# Drivers.net
KiCad netlist of a schematic drawn in Altium Designer
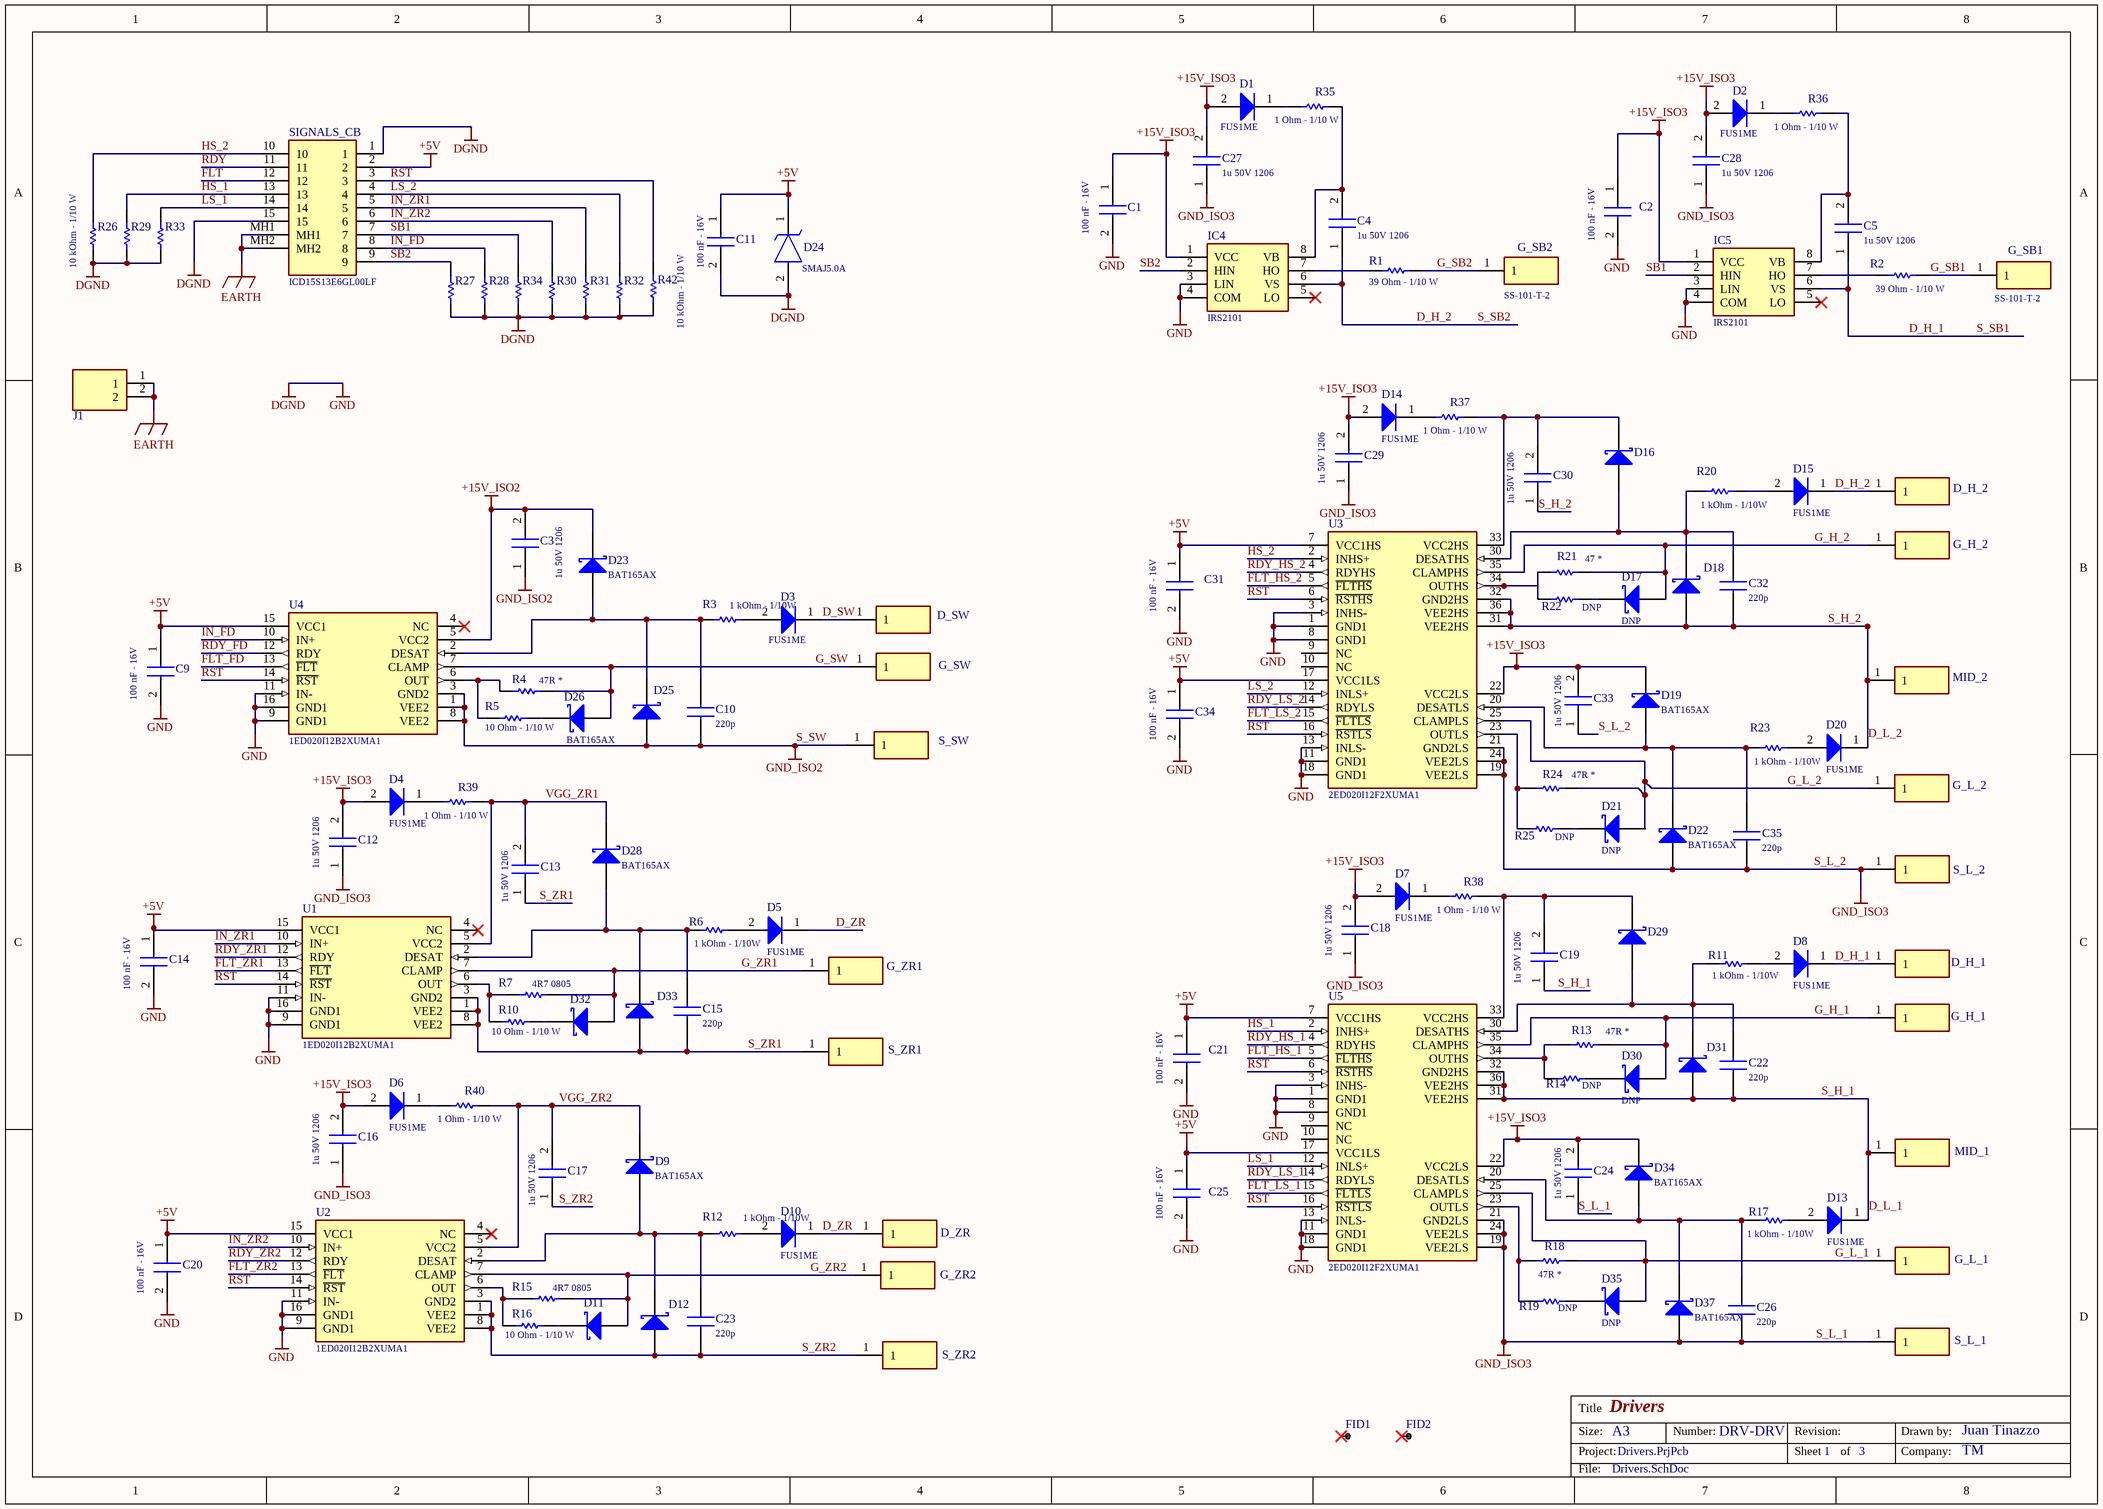
[diagram p0: Drivers.SchDoc]

(export (version "E")
  (design (tool "Eeschema 10.0.6"))
  (components
    (comp (ref "C1")
      (value "100 nF - 16V")
      (footprint "CAPC1608X95N")
      (description "Capacitor")
      (fields
        (field (name "MANUFACTURER_PART_NUMBER") "EMK107B7104KA-T")
        (field (name "MOUSER PART NUMBER") "963-EMK107B7104KA-T")
      )
      (libsource (lib "SamacSys") (part "EMK107B7104KA-T"))
    )
    (comp (ref "C2")
      (value "100 nF - 16V")
      (footprint "CAPC1608X95N")
      (description "Capacitor")
      (fields
        (field (name "MANUFACTURER_PART_NUMBER") "EMK107B7104KA-T")
        (field (name "MOUSER PART NUMBER") "963-EMK107B7104KA-T")
      )
      (libsource (lib "SamacSys") (part "EMK107B7104KA-T"))
    )
    (comp (ref "C3")
      (value "1u 50V 1206")
      (footprint "SamacSys:CAPC3216X180N")
      (description "Capacitor")
      (fields
        (field (name "MANUFACTURER_PART_NUMBER") "C3216X7R1H105K160AE")
        (field (name "MOUSER PART NUMBER") "810-C3216X7R1H105KST")
      )
      (libsource (lib "*") (part "C3216X7R1H105K160AE"))
    )
    (comp (ref "C4")
      (value "1u 50V 1206")
      (footprint "SamacSys:CAPC3216X180N")
      (description "Capacitor")
      (fields
        (field (name "MANUFACTURER_PART_NUMBER") "C3216X7R1H105K160AE")
        (field (name "MOUSER PART NUMBER") "810-C3216X7R1H105KST")
      )
      (libsource (lib "*") (part "C3216X7R1H105K160AE"))
    )
    (comp (ref "C5")
      (value "1u 50V 1206")
      (footprint "SamacSys:CAPC3216X180N")
      (description "Capacitor")
      (fields
        (field (name "MANUFACTURER_PART_NUMBER") "C3216X7R1H105K160AE")
        (field (name "MOUSER PART NUMBER") "810-C3216X7R1H105KST")
      )
      (libsource (lib "*") (part "C3216X7R1H105K160AE"))
    )
    (comp (ref "C9")
      (value "100 nF - 16V")
      (footprint "CAPC1608X95N")
      (description "Capacitor")
      (fields
        (field (name "MANUFACTURER_PART_NUMBER") "EMK107B7104KA-T")
        (field (name "MOUSER PART NUMBER") "963-EMK107B7104KA-T")
      )
      (libsource (lib "SamacSys") (part "EMK107B7104KA-T"))
    )
    (comp (ref "C10")
      (value "220p")
      (footprint "C0603")
      (description "Capacitor")
      (fields
        (field (name "MANUFACTURER_PART_NUMBER") "C0603C221J5HACAUTO")
        (field (name "MOUSER PART NUMBER") "80-C0603C221J5HAUTO")
      )
      (libsource (lib "SamacSys") (part "C0603C221J5HACAUTO"))
    )
    (comp (ref "C11")
      (value "100 nF - 16V")
      (footprint "CAPC1608X95N")
      (description "Capacitor")
      (fields
        (field (name "MANUFACTURER_PART_NUMBER") "EMK107B7104KA-T")
        (field (name "MOUSER PART NUMBER") "963-EMK107B7104KA-T")
      )
      (libsource (lib "SamacSys") (part "EMK107B7104KA-T"))
    )
    (comp (ref "C12")
      (value "1u 50V 1206")
      (footprint "SamacSys:CAPC3216X180N")
      (description "Capacitor")
      (fields
        (field (name "MANUFACTURER_PART_NUMBER") "C3216X7R1H105K160AE")
        (field (name "MOUSER PART NUMBER") "810-C3216X7R1H105KST")
      )
      (libsource (lib "*") (part "C3216X7R1H105K160AE"))
    )
    (comp (ref "C13")
      (value "1u 50V 1206")
      (footprint "SamacSys:CAPC3216X180N")
      (description "Capacitor")
      (fields
        (field (name "MANUFACTURER_PART_NUMBER") "C3216X7R1H105K160AE")
        (field (name "MOUSER PART NUMBER") "810-C3216X7R1H105KST")
      )
      (libsource (lib "*") (part "C3216X7R1H105K160AE"))
    )
    (comp (ref "C14")
      (value "100 nF - 16V")
      (footprint "CAPC1608X95N")
      (description "Capacitor")
      (fields
        (field (name "MANUFACTURER_PART_NUMBER") "EMK107B7104KA-T")
        (field (name "MOUSER PART NUMBER") "963-EMK107B7104KA-T")
      )
      (libsource (lib "SamacSys") (part "EMK107B7104KA-T"))
    )
    (comp (ref "C15")
      (value "220p")
      (footprint "C0603")
      (description "Capacitor")
      (fields
        (field (name "MANUFACTURER_PART_NUMBER") "C0603C221J5HACAUTO")
        (field (name "MOUSER PART NUMBER") "80-C0603C221J5HAUTO")
      )
      (libsource (lib "SamacSys") (part "C0603C221J5HACAUTO"))
    )
    (comp (ref "C16")
      (value "1u 50V 1206")
      (footprint "SamacSys:CAPC3216X180N")
      (description "Capacitor")
      (fields
        (field (name "MANUFACTURER_PART_NUMBER") "C3216X7R1H105K160AE")
        (field (name "MOUSER PART NUMBER") "810-C3216X7R1H105KST")
      )
      (libsource (lib "*") (part "C3216X7R1H105K160AE"))
    )
    (comp (ref "C17")
      (value "1u 50V 1206")
      (footprint "SamacSys:CAPC3216X180N")
      (description "Capacitor")
      (fields
        (field (name "MANUFACTURER_PART_NUMBER") "C3216X7R1H105K160AE")
        (field (name "MOUSER PART NUMBER") "810-C3216X7R1H105KST")
      )
      (libsource (lib "*") (part "C3216X7R1H105K160AE"))
    )
    (comp (ref "C18")
      (value "1u 50V 1206")
      (footprint "SamacSys:CAPC3216X180N")
      (description "Capacitor")
      (fields
        (field (name "MANUFACTURER_PART_NUMBER") "C3216X7R1H105K160AE")
        (field (name "MOUSER PART NUMBER") "810-C3216X7R1H105KST")
      )
      (libsource (lib "*") (part "C3216X7R1H105K160AE"))
    )
    (comp (ref "C19")
      (value "1u 50V 1206")
      (footprint "SamacSys:CAPC3216X180N")
      (description "Capacitor")
      (fields
        (field (name "MANUFACTURER_PART_NUMBER") "C3216X7R1H105K160AE")
        (field (name "MOUSER PART NUMBER") "810-C3216X7R1H105KST")
      )
      (libsource (lib "*") (part "C3216X7R1H105K160AE"))
    )
    (comp (ref "C20")
      (value "100 nF - 16V")
      (footprint "CAPC1608X95N")
      (description "Capacitor")
      (fields
        (field (name "MANUFACTURER_PART_NUMBER") "EMK107B7104KA-T")
        (field (name "MOUSER PART NUMBER") "963-EMK107B7104KA-T")
      )
      (libsource (lib "SamacSys") (part "EMK107B7104KA-T"))
    )
    (comp (ref "C21")
      (value "100 nF - 16V")
      (footprint "CAPC1608X95N")
      (description "Capacitor")
      (fields
        (field (name "MANUFACTURER_PART_NUMBER") "EMK107B7104KA-T")
        (field (name "MOUSER PART NUMBER") "963-EMK107B7104KA-T")
      )
      (libsource (lib "SamacSys") (part "EMK107B7104KA-T"))
    )
    (comp (ref "C22")
      (value "220p")
      (footprint "C0603")
      (description "Capacitor")
      (fields
        (field (name "MANUFACTURER_PART_NUMBER") "C0603C221J5HACAUTO")
        (field (name "MOUSER PART NUMBER") "80-C0603C221J5HAUTO")
      )
      (libsource (lib "SamacSys") (part "C0603C221J5HACAUTO"))
    )
    (comp (ref "C23")
      (value "220p")
      (footprint "C0603")
      (description "Capacitor")
      (fields
        (field (name "MANUFACTURER_PART_NUMBER") "C0603C221J5HACAUTO")
        (field (name "MOUSER PART NUMBER") "80-C0603C221J5HAUTO")
      )
      (libsource (lib "SamacSys") (part "C0603C221J5HACAUTO"))
    )
    (comp (ref "C24")
      (value "1u 50V 1206")
      (footprint "SamacSys:CAPC3216X180N")
      (description "Capacitor")
      (fields
        (field (name "MANUFACTURER_PART_NUMBER") "C3216X7R1H105K160AE")
        (field (name "MOUSER PART NUMBER") "810-C3216X7R1H105KST")
      )
      (libsource (lib "*") (part "C3216X7R1H105K160AE"))
    )
    (comp (ref "C25")
      (value "100 nF - 16V")
      (footprint "CAPC1608X95N")
      (description "Capacitor")
      (fields
        (field (name "MANUFACTURER_PART_NUMBER") "EMK107B7104KA-T")
        (field (name "MOUSER PART NUMBER") "963-EMK107B7104KA-T")
      )
      (libsource (lib "SamacSys") (part "EMK107B7104KA-T"))
    )
    (comp (ref "C26")
      (value "220p")
      (footprint "C0603")
      (description "Capacitor")
      (fields
        (field (name "MANUFACTURER_PART_NUMBER") "C0603C221J5HACAUTO")
        (field (name "MOUSER PART NUMBER") "80-C0603C221J5HAUTO")
      )
      (libsource (lib "SamacSys") (part "C0603C221J5HACAUTO"))
    )
    (comp (ref "C27")
      (value "1u 50V 1206")
      (footprint "SamacSys:CAPC3216X180N")
      (description "Capacitor")
      (fields
        (field (name "MANUFACTURER_PART_NUMBER") "C3216X7R1H105K160AE")
        (field (name "MOUSER PART NUMBER") "810-C3216X7R1H105KST")
      )
      (libsource (lib "*") (part "C3216X7R1H105K160AE"))
    )
    (comp (ref "C28")
      (value "1u 50V 1206")
      (footprint "SamacSys:CAPC3216X180N")
      (description "Capacitor")
      (fields
        (field (name "MANUFACTURER_PART_NUMBER") "C3216X7R1H105K160AE")
        (field (name "MOUSER PART NUMBER") "810-C3216X7R1H105KST")
      )
      (libsource (lib "*") (part "C3216X7R1H105K160AE"))
    )
    (comp (ref "C29")
      (value "1u 50V 1206")
      (footprint "SamacSys:CAPC3216X180N")
      (description "Capacitor")
      (fields
        (field (name "MANUFACTURER_PART_NUMBER") "C3216X7R1H105K160AE")
        (field (name "MOUSER PART NUMBER") "810-C3216X7R1H105KST")
      )
      (libsource (lib "*") (part "C3216X7R1H105K160AE"))
    )
    (comp (ref "C30")
      (value "1u 50V 1206")
      (footprint "SamacSys:CAPC3216X180N")
      (description "Capacitor")
      (fields
        (field (name "MANUFACTURER_PART_NUMBER") "C3216X7R1H105K160AE")
        (field (name "MOUSER PART NUMBER") "810-C3216X7R1H105KST")
      )
      (libsource (lib "*") (part "C3216X7R1H105K160AE"))
    )
    (comp (ref "C31")
      (value "100 nF - 16V")
      (footprint "CAPC1608X95N")
      (description "Capacitor")
      (fields
        (field (name "MANUFACTURER_PART_NUMBER") "EMK107B7104KA-T")
        (field (name "MOUSER PART NUMBER") "963-EMK107B7104KA-T")
      )
      (libsource (lib "SamacSys") (part "EMK107B7104KA-T"))
    )
    (comp (ref "C32")
      (value "220p")
      (footprint "C0603")
      (description "Capacitor")
      (fields
        (field (name "MANUFACTURER_PART_NUMBER") "C0603C221J5HACAUTO")
        (field (name "MOUSER PART NUMBER") "80-C0603C221J5HAUTO")
      )
      (libsource (lib "SamacSys") (part "C0603C221J5HACAUTO"))
    )
    (comp (ref "C33")
      (value "1u 50V 1206")
      (footprint "SamacSys:CAPC3216X180N")
      (description "Capacitor")
      (fields
        (field (name "MANUFACTURER_PART_NUMBER") "C3216X7R1H105K160AE")
        (field (name "MOUSER PART NUMBER") "810-C3216X7R1H105KST")
      )
      (libsource (lib "*") (part "C3216X7R1H105K160AE"))
    )
    (comp (ref "C34")
      (value "100 nF - 16V")
      (footprint "CAPC1608X95N")
      (description "Capacitor")
      (fields
        (field (name "MANUFACTURER_PART_NUMBER") "EMK107B7104KA-T")
        (field (name "MOUSER PART NUMBER") "963-EMK107B7104KA-T")
      )
      (libsource (lib "SamacSys") (part "EMK107B7104KA-T"))
    )
    (comp (ref "C35")
      (value "220p")
      (footprint "C0603")
      (description "Capacitor")
      (fields
        (field (name "MANUFACTURER_PART_NUMBER") "C0603C221J5HACAUTO")
        (field (name "MOUSER PART NUMBER") "80-C0603C221J5HAUTO")
      )
      (libsource (lib "SamacSys") (part "C0603C221J5HACAUTO"))
    )
    (comp (ref "D1")
      (value "FUS1ME")
      (footprint "SamacSys:SODFL3718X120N")
      (description "Diode")
      (fields (field (name "MOUSER PART NUMBER") "621-FUS1ME"))
      (libsource (lib "SamacSys") (part "FUS1ME"))
    )
    (comp (ref "D2")
      (value "FUS1ME")
      (footprint "SamacSys:SODFL3718X120N")
      (description "Diode")
      (fields (field (name "MOUSER PART NUMBER") "621-FUS1ME"))
      (libsource (lib "SamacSys") (part "FUS1ME"))
    )
    (comp (ref "D3")
      (value "FUS1ME")
      (footprint "SamacSys:SODFL3718X120N")
      (description "Diode")
      (fields (field (name "MOUSER PART NUMBER") "621-FUS1ME"))
      (libsource (lib "SamacSys") (part "FUS1ME"))
    )
    (comp (ref "D4")
      (value "FUS1ME")
      (footprint "SamacSys:SODFL3718X120N")
      (description "Diode")
      (fields (field (name "MOUSER PART NUMBER") "621-FUS1ME"))
      (libsource (lib "SamacSys") (part "FUS1ME"))
    )
    (comp (ref "D5")
      (value "FUS1ME")
      (footprint "SamacSys:SODFL3718X120N")
      (description "Diode")
      (fields (field (name "MOUSER PART NUMBER") "621-FUS1ME"))
      (libsource (lib "SamacSys") (part "FUS1ME"))
    )
    (comp (ref "D6")
      (value "FUS1ME")
      (footprint "SamacSys:SODFL3718X120N")
      (description "Diode")
      (fields (field (name "MOUSER PART NUMBER") "621-FUS1ME"))
      (libsource (lib "SamacSys") (part "FUS1ME"))
    )
    (comp (ref "D7")
      (value "FUS1ME")
      (footprint "SamacSys:SODFL3718X120N")
      (description "Diode")
      (fields (field (name "MOUSER PART NUMBER") "621-FUS1ME"))
      (libsource (lib "SamacSys") (part "FUS1ME"))
    )
    (comp (ref "D8")
      (value "FUS1ME")
      (footprint "SamacSys:SODFL3718X120N")
      (description "Diode")
      (fields (field (name "MOUSER PART NUMBER") "621-FUS1ME"))
      (libsource (lib "SamacSys") (part "FUS1ME"))
    )
    (comp (ref "D9")
      (value "BAT165AX")
      (footprint "BAT165AX")
      (description "Schottky Diode")
      (fields (field (name "MOUSER PART NUMBER") "771-BAT165AX"))
      (libsource (lib "SamacSys") (part "BAT165AX"))
    )
    (comp (ref "D10")
      (value "FUS1ME")
      (footprint "SamacSys:SODFL3718X120N")
      (description "Diode")
      (fields (field (name "MOUSER PART NUMBER") "621-FUS1ME"))
      (libsource (lib "SamacSys") (part "FUS1ME"))
    )
    (comp (ref "D11")
      (value "BAT165AX")
      (footprint "BAT165AX")
      (description "Schottky Diode")
      (fields (field (name "MOUSER PART NUMBER") "771-BAT165AX"))
      (libsource (lib "SamacSys") (part "BAT165AX"))
    )
    (comp (ref "D12")
      (value "BAT165AX")
      (footprint "BAT165AX")
      (description "Schottky Diode")
      (fields (field (name "MOUSER PART NUMBER") "771-BAT165AX"))
      (libsource (lib "SamacSys") (part "BAT165AX"))
    )
    (comp (ref "D13")
      (value "FUS1ME")
      (footprint "SamacSys:SODFL3718X120N")
      (description "Diode")
      (fields (field (name "MOUSER PART NUMBER") "621-FUS1ME"))
      (libsource (lib "SamacSys") (part "FUS1ME"))
    )
    (comp (ref "D14")
      (value "FUS1ME")
      (footprint "SamacSys:SODFL3718X120N")
      (description "Diode")
      (fields (field (name "MOUSER PART NUMBER") "621-FUS1ME"))
      (libsource (lib "SamacSys") (part "FUS1ME"))
    )
    (comp (ref "D15")
      (value "FUS1ME")
      (footprint "SamacSys:SODFL3718X120N")
      (description "Diode")
      (fields (field (name "MOUSER PART NUMBER") "621-FUS1ME"))
      (libsource (lib "SamacSys") (part "FUS1ME"))
    )
    (comp (ref "D16")
      (value "BAT165AX")
      (footprint "BAT165AX")
      (description "Schottky Diode")
      (fields (field (name "MOUSER PART NUMBER") "771-BAT165AX"))
      (libsource (lib "SamacSys") (part "BAT165AX"))
    )
    (comp (ref "D17")
      (value "DNP")
      (footprint "BAT165AX")
      (description "Schottky Diode")
      (fields
        (field (name "MANUFACTURER_PART_NUMBER") "BAT165AX")
        (field (name "MOUSER PART NUMBER") "771-BAT165AX")
      )
      (libsource (lib "SamacSys") (part "BAT165AX"))
    )
    (comp (ref "D18")
      (value "BAT165AX")
      (footprint "BAT165AX")
      (description "Schottky Diode")
      (fields (field (name "MOUSER PART NUMBER") "771-BAT165AX"))
      (libsource (lib "SamacSys") (part "BAT165AX"))
    )
    (comp (ref "D19")
      (value "BAT165AX")
      (footprint "BAT165AX")
      (description "Schottky Diode")
      (fields (field (name "MOUSER PART NUMBER") "771-BAT165AX"))
      (libsource (lib "SamacSys") (part "BAT165AX"))
    )
    (comp (ref "D20")
      (value "FUS1ME")
      (footprint "SamacSys:SODFL3718X120N")
      (description "Diode")
      (fields (field (name "MOUSER PART NUMBER") "621-FUS1ME"))
      (libsource (lib "SamacSys") (part "FUS1ME"))
    )
    (comp (ref "D21")
      (value "DNP")
      (footprint "BAT165AX")
      (description "Schottky Diode")
      (fields
        (field (name "MANUFACTURER_PART_NUMBER") "BAT165AX")
        (field (name "MOUSER PART NUMBER") "771-BAT165AX")
      )
      (libsource (lib "SamacSys") (part "BAT165AX"))
    )
    (comp (ref "D22")
      (value "BAT165AX")
      (footprint "BAT165AX")
      (description "Schottky Diode")
      (fields (field (name "MOUSER PART NUMBER") "771-BAT165AX"))
      (libsource (lib "SamacSys") (part "BAT165AX"))
    )
    (comp (ref "D23")
      (value "BAT165AX")
      (footprint "BAT165AX")
      (description "Schottky Diode")
      (fields (field (name "MOUSER PART NUMBER") "771-BAT165AX"))
      (libsource (lib "SamacSys") (part "BAT165AX"))
    )
    (comp (ref "D24")
      (value "SMAJ5.0A")
      (footprint "DIOM5026X229N")
      (description "TVS Diode (Uni-directional)")
      (fields (field (name "MOUSER PART NUMBER") "576-SMAJ5.0A"))
      (libsource (lib "SamacSys") (part "SMAJ5.0A"))
    )
    (comp (ref "D25")
      (value "BAT165AX")
      (footprint "BAT165AX")
      (description "Schottky Diode")
      (fields (field (name "MOUSER PART NUMBER") "771-BAT165AX"))
      (libsource (lib "SamacSys") (part "BAT165AX"))
    )
    (comp (ref "D26")
      (value "BAT165AX")
      (footprint "BAT165AX")
      (description "Schottky Diode")
      (fields (field (name "MOUSER PART NUMBER") "771-BAT165AX"))
      (libsource (lib "SamacSys") (part "BAT165AX"))
    )
    (comp (ref "D28")
      (value "BAT165AX")
      (footprint "BAT165AX")
      (description "Schottky Diode")
      (fields (field (name "MOUSER PART NUMBER") "771-BAT165AX"))
      (libsource (lib "SamacSys") (part "BAT165AX"))
    )
    (comp (ref "D29")
      (value "BAT165AX")
      (footprint "BAT165AX")
      (description "Schottky Diode")
      (fields (field (name "MOUSER PART NUMBER") "771-BAT165AX"))
      (libsource (lib "SamacSys") (part "BAT165AX"))
    )
    (comp (ref "D30")
      (value "DNP")
      (footprint "BAT165AX")
      (description "Schottky Diode")
      (fields
        (field (name "MANUFACTURER_PART_NUMBER") "BAT165AX")
        (field (name "MOUSER PART NUMBER") "771-BAT165AX")
      )
      (libsource (lib "SamacSys") (part "BAT165AX"))
    )
    (comp (ref "D31")
      (value "BAT165AX")
      (footprint "BAT165AX")
      (description "Schottky Diode")
      (fields (field (name "MOUSER PART NUMBER") "771-BAT165AX"))
      (libsource (lib "SamacSys") (part "BAT165AX"))
    )
    (comp (ref "D32")
      (value "BAT165AX")
      (footprint "BAT165AX")
      (description "Schottky Diode")
      (fields (field (name "MOUSER PART NUMBER") "771-BAT165AX"))
      (libsource (lib "SamacSys") (part "BAT165AX"))
    )
    (comp (ref "D33")
      (value "BAT165AX")
      (footprint "BAT165AX")
      (description "Schottky Diode")
      (fields (field (name "MOUSER PART NUMBER") "771-BAT165AX"))
      (libsource (lib "SamacSys") (part "BAT165AX"))
    )
    (comp (ref "D34")
      (value "BAT165AX")
      (footprint "BAT165AX")
      (description "Schottky Diode")
      (fields (field (name "MOUSER PART NUMBER") "771-BAT165AX"))
      (libsource (lib "SamacSys") (part "BAT165AX"))
    )
    (comp (ref "D35")
      (value "DNP")
      (footprint "BAT165AX")
      (description "Schottky Diode")
      (fields
        (field (name "MANUFACTURER_PART_NUMBER") "BAT165AX")
        (field (name "MOUSER PART NUMBER") "771-BAT165AX")
      )
      (libsource (lib "SamacSys") (part "BAT165AX"))
    )
    (comp (ref "D37")
      (value "BAT165AX")
      (footprint "BAT165AX")
      (description "Schottky Diode")
      (fields (field (name "MOUSER PART NUMBER") "771-BAT165AX"))
      (libsource (lib "SamacSys") (part "BAT165AX"))
    )
    (comp (ref "D_H_1")
      (value "SS-101-T-2")
      (footprint "SS-101-XX-2")
      (description "Connector")
      (fields (field (name "MOUSER PART NUMBER") "200-SS101T2"))
      (libsource (lib "SamacSys") (part "SS-101-T-2"))
    )
    (comp (ref "D_H_2")
      (value "SS-101-T-2")
      (footprint "SS-101-XX-2")
      (description "Connector")
      (fields (field (name "MOUSER PART NUMBER") "200-SS101T2"))
      (libsource (lib "SamacSys") (part "SS-101-T-2"))
    )
    (comp (ref "D_SW")
      (value "D_SW")
      (footprint "SS-101-XX-2")
      (description "Connector")
      (fields
        (field (name "MOUSER PART NUMBER") "200-SS101T2")
        (field (name "MANUFACTURER_PART_NUMBER") "SS-101-T-2")
      )
      (libsource (lib "SamacSys") (part "SS-101-T-2"))
    )
    (comp (ref "D_ZR")
      (value "SS-101-T-2")
      (footprint "SS-101-XX-2")
      (description "Connector")
      (fields (field (name "MOUSER PART NUMBER") "200-SS101T2"))
      (libsource (lib "SamacSys") (part "SS-101-T-2"))
    )
    (comp (ref "FID1")
      (value "Fiducial")
      (footprint "Fiducial")
      (libsource (lib "Libreria1") (part "Fiducial"))
    )
    (comp (ref "FID2")
      (value "Fiducial")
      (footprint "Fiducial")
      (libsource (lib "Libreria1") (part "Fiducial"))
    )
    (comp (ref "G_H_1")
      (value "SS-101-T-2")
      (footprint "SS-101-XX-2")
      (description "Connector")
      (fields (field (name "MOUSER PART NUMBER") "200-SS101T2"))
      (libsource (lib "SamacSys") (part "SS-101-T-2"))
    )
    (comp (ref "G_H_2")
      (value "SS-101-T-2")
      (footprint "SS-101-XX-2")
      (description "Connector")
      (fields (field (name "MOUSER PART NUMBER") "200-SS101T2"))
      (libsource (lib "SamacSys") (part "SS-101-T-2"))
    )
    (comp (ref "G_L_1")
      (value "SS-101-T-2")
      (footprint "SS-101-XX-2")
      (description "Connector")
      (fields (field (name "MOUSER PART NUMBER") "200-SS101T2"))
      (libsource (lib "SamacSys") (part "SS-101-T-2"))
    )
    (comp (ref "G_L_2")
      (value "SS-101-T-2")
      (footprint "SS-101-XX-2")
      (description "Connector")
      (fields (field (name "MOUSER PART NUMBER") "200-SS101T2"))
      (libsource (lib "SamacSys") (part "SS-101-T-2"))
    )
    (comp (ref "G_SB1")
      (value "SS-101-T-2")
      (footprint "SS-101-XX-2")
      (description "Connector")
      (fields (field (name "MOUSER PART NUMBER") "200-SS101T2"))
      (libsource (lib "SamacSys") (part "SS-101-T-2"))
    )
    (comp (ref "G_SB2")
      (value "SS-101-T-2")
      (footprint "SS-101-XX-2")
      (description "Connector")
      (fields (field (name "MOUSER PART NUMBER") "200-SS101T2"))
      (libsource (lib "SamacSys") (part "SS-101-T-2"))
    )
    (comp (ref "G_SW")
      (value "G_SW")
      (footprint "SS-101-XX-2")
      (description "Connector")
      (fields
        (field (name "MOUSER PART NUMBER") "200-SS101T2")
        (field (name "MANUFACTURER_PART_NUMBER") "SS-101-T-2")
      )
      (libsource (lib "SamacSys") (part "SS-101-T-2"))
    )
    (comp (ref "G_ZR1")
      (value "SS-101-T-2")
      (footprint "SS-101-XX-2")
      (description "Connector")
      (fields (field (name "MOUSER PART NUMBER") "200-SS101T2"))
      (libsource (lib "SamacSys") (part "SS-101-T-2"))
    )
    (comp (ref "G_ZR2")
      (value "SS-101-T-2")
      (footprint "SS-101-XX-2")
      (description "Connector")
      (fields (field (name "MOUSER PART NUMBER") "200-SS101T2"))
      (libsource (lib "SamacSys") (part "SS-101-T-2"))
    )
    (comp (ref "IC4")
      (value "IRS2101")
      (footprint "SamacSys:SOIC127P600X175-8N")
      (description "Integrated Circuit")
      (fields
        (field (name "MANUFACTURER_PART_NUMBER") "IRS2101STRPBF")
        (field (name "MOUSER PART NUMBER") "942-IRS2101STRPBF")
      )
      (libsource (lib "*") (part "IRS2101STRPBF"))
    )
    (comp (ref "IC5")
      (value "IRS2101")
      (footprint "SamacSys:SOIC127P600X175-8N")
      (description "Integrated Circuit")
      (fields
        (field (name "MANUFACTURER_PART_NUMBER") "IRS2101STRPBF")
        (field (name "MOUSER PART NUMBER") "942-IRS2101STRPBF")
      )
      (libsource (lib "*") (part "IRS2101STRPBF"))
    )
    (comp (ref "J1")
      (value "19705-4303")
      (footprint "197054303")
      (description "Connector")
      (libsource (lib "SamacSys") (part "19705-4303"))
    )
    (comp (ref "MID_1")
      (value "SS-101-T-2")
      (footprint "SS-101-XX-2")
      (description "Connector")
      (fields (field (name "MOUSER PART NUMBER") "200-SS101T2"))
      (libsource (lib "SamacSys") (part "SS-101-T-2"))
    )
    (comp (ref "MID_2")
      (value "SS-101-T-2")
      (footprint "SS-101-XX-2")
      (description "Connector")
      (fields (field (name "MOUSER PART NUMBER") "200-SS101T2"))
      (libsource (lib "SamacSys") (part "SS-101-T-2"))
    )
    (comp (ref "R1")
      (value "39 Ohm - 1/10 W")
      (footprint "RESC1608X55N")
      (description "Resistor")
      (fields
        (field (name "MANUFACTURER_PART_NUMBER") "CRCW0603150RFKEBC")
        (field (name "MOUSER PART NUMBER") "71-CRCW0603150RFKEBC")
      )
      (libsource (lib "SamacSys") (part "CRCW0603150RFKEBC"))
    )
    (comp (ref "R2")
      (value "39 Ohm - 1/10 W")
      (footprint "RESC1608X55N")
      (description "Resistor")
      (fields
        (field (name "MANUFACTURER_PART_NUMBER") "CRCW0603150RFKEBC")
        (field (name "MOUSER PART NUMBER") "71-CRCW0603150RFKEBC")
      )
      (libsource (lib "SamacSys") (part "CRCW0603150RFKEBC"))
    )
    (comp (ref "R3")
      (value "1 kOhm - 1/10W")
      (footprint "RESC1608X55N")
      (description "Resistor")
      (fields
        (field (name "MANUFACTURER_PART_NUMBER") "CRCW06031K00FKEAC")
        (field (name "MOUSER PART NUMBER") "71-CRCW06031K00FKEAC")
      )
      (libsource (lib "SamacSys") (part "CRCW06031K00FKEAC"))
    )
    (comp (ref "R4")
      (value "47R *")
      (footprint "SamacSys:RESC2012X60N")
      (description "Resistor")
      (fields
        (field (name "MANUFACTURER_PART_NUMBER") "CR0805-J/-4R7ELF")
        (field (name "MOUSER PART NUMBER") "652-CR0805-J/-4R7ELF")
      )
      (libsource (lib "SamacSys") (part "CR0805-J_-4R7ELF"))
    )
    (comp (ref "R5")
      (value "10 Ohm - 1/10 W")
      (footprint "RESC1608X50N")
      (description "Resistor")
      (fields
        (field (name "MANUFACTURER_PART_NUMBER") "CRCW060310R0FKEAHP")
        (field (name "MOUSER PART NUMBER") "71-CRCW060310R0FKEAH")
      )
      (libsource (lib "SamacSys") (part "CRCW060310R0FKEAHP"))
    )
    (comp (ref "R6")
      (value "1 kOhm - 1/10W")
      (footprint "RESC1608X55N")
      (description "Resistor")
      (fields
        (field (name "MANUFACTURER_PART_NUMBER") "CRCW06031K00FKEAC")
        (field (name "MOUSER PART NUMBER") "71-CRCW06031K00FKEAC")
      )
      (libsource (lib "SamacSys") (part "CRCW06031K00FKEAC"))
    )
    (comp (ref "R7")
      (value "4R7 0805")
      (footprint "SamacSys:RESC2012X60N")
      (description "Resistor")
      (fields
        (field (name "MANUFACTURER_PART_NUMBER") "CR0805-J/-4R7ELF")
        (field (name "MOUSER PART NUMBER") "652-CR0805-J/-4R7ELF")
      )
      (libsource (lib "SamacSys") (part "CR0805-J_-4R7ELF"))
    )
    (comp (ref "R10")
      (value "10 Ohm - 1/10 W")
      (footprint "RESC1608X50N")
      (description "Resistor")
      (fields
        (field (name "MANUFACTURER_PART_NUMBER") "CRCW060310R0FKEAHP")
        (field (name "MOUSER PART NUMBER") "71-CRCW060310R0FKEAH")
      )
      (libsource (lib "SamacSys") (part "CRCW060310R0FKEAHP"))
    )
    (comp (ref "R11")
      (value "1 kOhm - 1/10W")
      (footprint "RESC1608X55N")
      (description "Resistor")
      (fields
        (field (name "MANUFACTURER_PART_NUMBER") "CRCW06031K00FKEAC")
        (field (name "MOUSER PART NUMBER") "71-CRCW06031K00FKEAC")
      )
      (libsource (lib "SamacSys") (part "CRCW06031K00FKEAC"))
    )
    (comp (ref "R12")
      (value "1 kOhm - 1/10W")
      (footprint "RESC1608X55N")
      (description "Resistor")
      (fields
        (field (name "MANUFACTURER_PART_NUMBER") "CRCW06031K00FKEAC")
        (field (name "MOUSER PART NUMBER") "71-CRCW06031K00FKEAC")
      )
      (libsource (lib "SamacSys") (part "CRCW06031K00FKEAC"))
    )
    (comp (ref "R13")
      (value "47R *")
      (footprint "SamacSys:RESC2012X60N")
      (description "Resistor")
      (fields
        (field (name "MANUFACTURER_PART_NUMBER") "CR0805-J/-4R7ELF")
        (field (name "MOUSER PART NUMBER") "652-CR0805-J/-4R7ELF")
      )
      (libsource (lib "SamacSys") (part "CR0805-J_-4R7ELF"))
    )
    (comp (ref "R14")
      (value "DNP")
      (footprint "RESC1608X50N")
      (description "Resistor")
      (fields
        (field (name "MANUFACTURER_PART_NUMBER") "CRCW060310R0FKEAHP")
        (field (name "MOUSER PART NUMBER") "71-CRCW060310R0FKEAH")
      )
      (libsource (lib "SamacSys") (part "CRCW060310R0FKEAHP"))
    )
    (comp (ref "R15")
      (value "4R7 0805")
      (footprint "SamacSys:RESC2012X60N")
      (description "Resistor")
      (fields
        (field (name "MANUFACTURER_PART_NUMBER") "CR0805-J/-4R7ELF")
        (field (name "MOUSER PART NUMBER") "652-CR0805-J/-4R7ELF")
      )
      (libsource (lib "SamacSys") (part "CR0805-J_-4R7ELF"))
    )
    (comp (ref "R16")
      (value "10 Ohm - 1/10 W")
      (footprint "RESC1608X50N")
      (description "Resistor")
      (fields
        (field (name "MANUFACTURER_PART_NUMBER") "CRCW060310R0FKEAHP")
        (field (name "MOUSER PART NUMBER") "71-CRCW060310R0FKEAH")
      )
      (libsource (lib "SamacSys") (part "CRCW060310R0FKEAHP"))
    )
    (comp (ref "R17")
      (value "1 kOhm - 1/10W")
      (footprint "RESC1608X55N")
      (description "Resistor")
      (fields
        (field (name "MANUFACTURER_PART_NUMBER") "CRCW06031K00FKEAC")
        (field (name "MOUSER PART NUMBER") "71-CRCW06031K00FKEAC")
      )
      (libsource (lib "SamacSys") (part "CRCW06031K00FKEAC"))
    )
    (comp (ref "R18")
      (value "47R *")
      (footprint "SamacSys:RESC2012X60N")
      (description "Resistor")
      (fields
        (field (name "MANUFACTURER_PART_NUMBER") "CR0805-J/-4R7ELF")
        (field (name "MOUSER PART NUMBER") "652-CR0805-J/-4R7ELF")
      )
      (libsource (lib "SamacSys") (part "CR0805-J_-4R7ELF"))
    )
    (comp (ref "R19")
      (value "DNP")
      (footprint "RESC1608X50N")
      (description "Resistor")
      (fields
        (field (name "MANUFACTURER_PART_NUMBER") "CRCW060310R0FKEAHP")
        (field (name "MOUSER PART NUMBER") "71-CRCW060310R0FKEAH")
      )
      (libsource (lib "SamacSys") (part "CRCW060310R0FKEAHP"))
    )
    (comp (ref "R20")
      (value "1 kOhm - 1/10W")
      (footprint "RESC1608X55N")
      (description "Resistor")
      (fields
        (field (name "MANUFACTURER_PART_NUMBER") "CRCW06031K00FKEAC")
        (field (name "MOUSER PART NUMBER") "71-CRCW06031K00FKEAC")
      )
      (libsource (lib "SamacSys") (part "CRCW06031K00FKEAC"))
    )
    (comp (ref "R21")
      (value "47 *")
      (footprint "SamacSys:RESC2012X60N")
      (description "Resistor")
      (fields
        (field (name "MANUFACTURER_PART_NUMBER") "CR0805-J/-4R7ELF")
        (field (name "MOUSER PART NUMBER") "652-CR0805-J/-4R7ELF")
      )
      (libsource (lib "SamacSys") (part "CR0805-J_-4R7ELF"))
    )
    (comp (ref "R22")
      (value "DNP")
      (footprint "RESC1608X50N")
      (description "Resistor")
      (fields
        (field (name "MANUFACTURER_PART_NUMBER") "CRCW060310R0FKEAHP")
        (field (name "MOUSER PART NUMBER") "71-CRCW060310R0FKEAH")
      )
      (libsource (lib "SamacSys") (part "CRCW060310R0FKEAHP"))
    )
    (comp (ref "R23")
      (value "1 kOhm - 1/10W")
      (footprint "RESC1608X55N")
      (description "Resistor")
      (fields
        (field (name "MANUFACTURER_PART_NUMBER") "CRCW06031K00FKEAC")
        (field (name "MOUSER PART NUMBER") "71-CRCW06031K00FKEAC")
      )
      (libsource (lib "SamacSys") (part "CRCW06031K00FKEAC"))
    )
    (comp (ref "R24")
      (value "47R *")
      (footprint "SamacSys:RESC2012X60N")
      (description "Resistor")
      (fields
        (field (name "MANUFACTURER_PART_NUMBER") "CR0805-J/-4R7ELF")
        (field (name "MOUSER PART NUMBER") "652-CR0805-J/-4R7ELF")
      )
      (libsource (lib "SamacSys") (part "CR0805-J_-4R7ELF"))
    )
    (comp (ref "R25")
      (value "DNP")
      (footprint "RESC1608X50N")
      (description "Resistor")
      (fields
        (field (name "MANUFACTURER_PART_NUMBER") "CRCW060310R0FKEAHP")
        (field (name "MOUSER PART NUMBER") "71-CRCW060310R0FKEAH")
      )
      (libsource (lib "SamacSys") (part "CRCW060310R0FKEAHP"))
    )
    (comp (ref "R26")
      (value "10 kOhm - 1/10 W")
      (footprint "RESC1608X55N")
      (description "Resistor")
      (fields
        (field (name "MANUFACTURER_PART_NUMBER") "RMC1/16K1002FTP")
        (field (name "Comment") "RMC1_16K1002FTP")
      )
      (libsource (lib "SamacSys") (part "RMC1_16K1002FTP"))
    )
    (comp (ref "R27")
      (value "RMC1_16K1002FTP")
      (footprint "RESC1608X55N")
      (description "Resistor")
      (fields (field (name "MANUFACTURER_PART_NUMBER") "RMC1/16K1002FTP"))
      (libsource (lib "SamacSys") (part "RMC1_16K1002FTP"))
    )
    (comp (ref "R28")
      (value "RMC1_16K1002FTP")
      (footprint "RESC1608X55N")
      (description "Resistor")
      (fields (field (name "MANUFACTURER_PART_NUMBER") "RMC1/16K1002FTP"))
      (libsource (lib "SamacSys") (part "RMC1_16K1002FTP"))
    )
    (comp (ref "R29")
      (value "RMC1_16K1002FTP")
      (footprint "RESC1608X55N")
      (description "Resistor")
      (fields (field (name "MANUFACTURER_PART_NUMBER") "RMC1/16K1002FTP"))
      (libsource (lib "SamacSys") (part "RMC1_16K1002FTP"))
    )
    (comp (ref "R30")
      (value "RMC1_16K1002FTP")
      (footprint "RESC1608X55N")
      (description "Resistor")
      (fields (field (name "MANUFACTURER_PART_NUMBER") "RMC1/16K1002FTP"))
      (libsource (lib "SamacSys") (part "RMC1_16K1002FTP"))
    )
    (comp (ref "R31")
      (value "RMC1_16K1002FTP")
      (footprint "RESC1608X55N")
      (description "Resistor")
      (fields (field (name "MANUFACTURER_PART_NUMBER") "RMC1/16K1002FTP"))
      (libsource (lib "SamacSys") (part "RMC1_16K1002FTP"))
    )
    (comp (ref "R32")
      (value "RMC1_16K1002FTP")
      (footprint "RESC1608X55N")
      (description "Resistor")
      (fields (field (name "MANUFACTURER_PART_NUMBER") "RMC1/16K1002FTP"))
      (libsource (lib "SamacSys") (part "RMC1_16K1002FTP"))
    )
    (comp (ref "R33")
      (value "RMC1_16K1002FTP")
      (footprint "RESC1608X55N")
      (description "Resistor")
      (fields (field (name "MANUFACTURER_PART_NUMBER") "RMC1/16K1002FTP"))
      (libsource (lib "SamacSys") (part "RMC1_16K1002FTP"))
    )
    (comp (ref "R34")
      (value "RMC1_16K1002FTP")
      (footprint "RESC1608X55N")
      (description "Resistor")
      (fields (field (name "MANUFACTURER_PART_NUMBER") "RMC1/16K1002FTP"))
      (libsource (lib "SamacSys") (part "RMC1_16K1002FTP"))
    )
    (comp (ref "R35")
      (value "1 Ohm - 1/10 W")
      (footprint "SamacSys:RESC1608X55N")
      (description "Resistor")
      (fields
        (field (name "MANUFACTURER_PART_NUMBER") "CR0603-F/-1R00ELF")
        (field (name "MOUSER PART NUMBER") "652-CR0603-F/1R00ELF")
      )
      (libsource (lib "SamacSys") (part "CR0603-F_-1R00ELF"))
    )
    (comp (ref "R36")
      (value "1 Ohm - 1/10 W")
      (footprint "SamacSys:RESC1608X55N")
      (description "Resistor")
      (fields
        (field (name "MANUFACTURER_PART_NUMBER") "CR0603-F/-1R00ELF")
        (field (name "MOUSER PART NUMBER") "652-CR0603-F/1R00ELF")
      )
      (libsource (lib "SamacSys") (part "CR0603-F_-1R00ELF"))
    )
    (comp (ref "R37")
      (value "1 Ohm - 1/10 W")
      (footprint "SamacSys:RESC1608X55N")
      (description "Resistor")
      (fields
        (field (name "MANUFACTURER_PART_NUMBER") "CR0603-F/-1R00ELF")
        (field (name "MOUSER PART NUMBER") "652-CR0603-F/1R00ELF")
      )
      (libsource (lib "SamacSys") (part "CR0603-F_-1R00ELF"))
    )
    (comp (ref "R38")
      (value "1 Ohm - 1/10 W")
      (footprint "SamacSys:RESC1608X55N")
      (description "Resistor")
      (fields
        (field (name "MANUFACTURER_PART_NUMBER") "CR0603-F/-1R00ELF")
        (field (name "MOUSER PART NUMBER") "652-CR0603-F/1R00ELF")
      )
      (libsource (lib "SamacSys") (part "CR0603-F_-1R00ELF"))
    )
    (comp (ref "R39")
      (value "1 Ohm - 1/10 W")
      (footprint "SamacSys:RESC1608X55N")
      (description "Resistor")
      (fields
        (field (name "MANUFACTURER_PART_NUMBER") "CR0603-F/-1R00ELF")
        (field (name "MOUSER PART NUMBER") "652-CR0603-F/1R00ELF")
      )
      (libsource (lib "SamacSys") (part "CR0603-F_-1R00ELF"))
    )
    (comp (ref "R40")
      (value "1 Ohm - 1/10 W")
      (footprint "SamacSys:RESC1608X55N")
      (description "Resistor")
      (fields
        (field (name "MANUFACTURER_PART_NUMBER") "CR0603-F/-1R00ELF")
        (field (name "MOUSER PART NUMBER") "652-CR0603-F/1R00ELF")
      )
      (libsource (lib "SamacSys") (part "CR0603-F_-1R00ELF"))
    )
    (comp (ref "R42")
      (value "10 kOhm - 1/10 W")
      (footprint "RESC1608X55N")
      (description "Resistor")
      (fields
        (field (name "MANUFACTURER_PART_NUMBER") "RMC1/16K1002FTP")
        (field (name "Comment") "RMC1_16K1002FTP")
      )
      (libsource (lib "SamacSys") (part "RMC1_16K1002FTP"))
    )
    (comp (ref "SIGNALS_CB")
      (value "ICD15S13E6GL00LF")
      (footprint "SamacSys:ICD15S13E6GL00LF")
      (description "Connector")
      (libsource (lib "*") (part "ICD15S13E6GL00LF"))
    )
    (comp (ref "S_L_1")
      (value "SS-101-T-2")
      (footprint "SS-101-XX-2")
      (description "Connector")
      (fields (field (name "MOUSER PART NUMBER") "200-SS101T2"))
      (libsource (lib "SamacSys") (part "SS-101-T-2"))
    )
    (comp (ref "S_L_2")
      (value "SS-101-T-2")
      (footprint "SS-101-XX-2")
      (description "Connector")
      (fields (field (name "MOUSER PART NUMBER") "200-SS101T2"))
      (libsource (lib "SamacSys") (part "SS-101-T-2"))
    )
    (comp (ref "S_SW")
      (value "S_SW")
      (footprint "SS-101-XX-2")
      (description "Connector")
      (fields
        (field (name "MANUFACTURER_PART_NUMBER") "SS-101-T-2")
        (field (name "MOUSER PART NUMBER") "200-SS101T2")
      )
      (libsource (lib "SamacSys") (part "SS-101-T-2"))
    )
    (comp (ref "S_ZR1")
      (value "SS-101-T-2")
      (footprint "SS-101-XX-2")
      (description "Connector")
      (fields (field (name "MOUSER PART NUMBER") "200-SS101T2"))
      (libsource (lib "SamacSys") (part "SS-101-T-2"))
    )
    (comp (ref "S_ZR2")
      (value "SS-101-T-2")
      (footprint "SS-101-XX-2")
      (description "Connector")
      (fields (field (name "MOUSER PART NUMBER") "200-SS101T2"))
      (libsource (lib "SamacSys") (part "SS-101-T-2"))
    )
    (comp (ref "U1")
      (value "1ED020I12B2XUMA1")
      (footprint "SOIC127P1028X264-16N")
      (description "Integrated Circuit")
      (fields (field (name "MOUSER PART NUMBER") "726-1ED020I12B2XUMA1"))
      (libsource (lib "SamacSys") (part "1ED020I12B2XUMA1"))
    )
    (comp (ref "U2")
      (value "1ED020I12B2XUMA1")
      (footprint "SOIC127P1028X264-16N")
      (description "Integrated Circuit")
      (fields (field (name "MOUSER PART NUMBER") "726-1ED020I12B2XUMA1"))
      (libsource (lib "SamacSys") (part "1ED020I12B2XUMA1"))
    )
    (comp (ref "U3")
      (value "2ED020I12F2XUMA1")
      (footprint "2ED020I12F2XUMA1")
      (description "Integrated Circuit")
      (fields (field (name "MOUSER PART NUMBER") "726-2ED020I12F2XUMA1"))
      (libsource (lib "SamacSys") (part "2ED020I12F2XUMA1"))
    )
    (comp (ref "U4")
      (value "1ED020I12B2XUMA1")
      (footprint "SOIC127P1028X264-16N")
      (description "Integrated Circuit")
      (fields (field (name "MOUSER PART NUMBER") "726-1ED020I12B2XUMA1"))
      (libsource (lib "SamacSys") (part "1ED020I12B2XUMA1"))
    )
    (comp (ref "U5")
      (value "2ED020I12F2XUMA1")
      (footprint "2ED020I12F2XUMA1")
      (description "Integrated Circuit")
      (fields (field (name "MOUSER PART NUMBER") "726-2ED020I12F2XUMA1"))
      (libsource (lib "SamacSys") (part "2ED020I12F2XUMA1"))
    )
  )
  (nets
    (net (code "1") (name "+5V") (class "Default")
      (node (ref "C11") (pin "1") (pinfunction "1_1") (pintype "passive"))
      (node (ref "C14") (pin "1") (pinfunction "1_1") (pintype "passive"))
      (node (ref "C20") (pin "1") (pinfunction "1_1") (pintype "passive"))
      (node (ref "C21") (pin "1") (pinfunction "1_1") (pintype "passive"))
      (node (ref "C25") (pin "1") (pinfunction "1_1") (pintype "passive"))
      (node (ref "C31") (pin "1") (pinfunction "1_1") (pintype "passive"))
      (node (ref "C34") (pin "1") (pinfunction "1_1") (pintype "passive"))
      (node (ref "C9") (pin "1") (pinfunction "1_1") (pintype "passive"))
      (node (ref "D24") (pin "1") (pinfunction "K_1") (pintype "passive"))
      (node (ref "SIGNALS_CB") (pin "2") (pinfunction "2_2") (pintype "passive"))
      (node (ref "U1") (pin "15") (pinfunction "VCC1_15") (pintype "power_in"))
      (node (ref "U2") (pin "15") (pinfunction "VCC1_15") (pintype "power_in"))
      (node (ref "U3") (pin "17") (pinfunction "VCC1LS_17") (pintype "passive"))
      (node (ref "U3") (pin "7") (pinfunction "VCC1HS_7") (pintype "passive"))
      (node (ref "U4") (pin "15") (pinfunction "VCC1_15") (pintype "power_in"))
      (node (ref "U5") (pin "17") (pinfunction "VCC1LS_17") (pintype "passive"))
      (node (ref "U5") (pin "7") (pinfunction "VCC1HS_7") (pintype "passive"))
    )
    (net (code "2") (name "+15V_ISO2") (class "Default")
      (node (ref "C3") (pin "2") (pinfunction "2_2") (pintype "passive"))
      (node (ref "D23") (pin "1") (pinfunction "K_1") (pintype "passive"))
      (node (ref "U4") (pin "5") (pinfunction "VCC2_5") (pintype "power_in"))
    )
    (net (code "3") (name "+15V_ISO3") (class "Default")
      (node (ref "C1") (pin "1") (pinfunction "1_1") (pintype "passive"))
      (node (ref "C12") (pin "2") (pinfunction "2_2") (pintype "passive"))
      (node (ref "C16") (pin "2") (pinfunction "2_2") (pintype "passive"))
      (node (ref "C18") (pin "2") (pinfunction "2_2") (pintype "passive"))
      (node (ref "C2") (pin "1") (pinfunction "1_1") (pintype "passive"))
      (node (ref "C24") (pin "2") (pinfunction "2_2") (pintype "passive"))
      (node (ref "C27") (pin "2") (pinfunction "2_2") (pintype "passive"))
      (node (ref "C28") (pin "2") (pinfunction "2_2") (pintype "passive"))
      (node (ref "C29") (pin "2") (pinfunction "2_2") (pintype "passive"))
      (node (ref "C33") (pin "2") (pinfunction "2_2") (pintype "passive"))
      (node (ref "D1") (pin "2") (pinfunction "A_2") (pintype "passive"))
      (node (ref "D14") (pin "2") (pinfunction "A_2") (pintype "passive"))
      (node (ref "D19") (pin "1") (pinfunction "K_1") (pintype "passive"))
      (node (ref "D2") (pin "2") (pinfunction "A_2") (pintype "passive"))
      (node (ref "D34") (pin "1") (pinfunction "K_1") (pintype "passive"))
      (node (ref "D4") (pin "2") (pinfunction "A_2") (pintype "passive"))
      (node (ref "D6") (pin "2") (pinfunction "A_2") (pintype "passive"))
      (node (ref "D7") (pin "2") (pinfunction "A_2") (pintype "passive"))
      (node (ref "IC4") (pin "1") (pinfunction "VCC_1") (pintype "passive"))
      (node (ref "IC5") (pin "1") (pinfunction "VCC_1") (pintype "passive"))
      (node (ref "U3") (pin "22") (pinfunction "VCC2LS_22") (pintype "passive"))
      (node (ref "U5") (pin "22") (pinfunction "VCC2LS_22") (pintype "passive"))
    )
    (net (code "4") (name "/D_H_1") (class "Default")
      (node (ref "C5") (pin "1") (pinfunction "1_1") (pintype "passive"))
      (node (ref "D8") (pin "1") (pinfunction "K_1") (pintype "passive"))
      (node (ref "D_H_1") (pin "1") (pinfunction "1_1") (pintype "passive"))
      (node (ref "IC5") (pin "6") (pinfunction "VS_6") (pintype "passive"))
    )
    (net (code "5") (name "/D_H_2") (class "Default")
      (node (ref "C4") (pin "1") (pinfunction "1_1") (pintype "passive"))
      (node (ref "D15") (pin "1") (pinfunction "K_1") (pintype "passive"))
      (node (ref "D_H_2") (pin "1") (pinfunction "1_1") (pintype "passive"))
      (node (ref "IC4") (pin "6") (pinfunction "VS_6") (pintype "passive"))
    )
    (net (code "6") (name "/D_L_1") (class "Default")
      (node (ref "C19") (pin "1") (pinfunction "1_1") (pintype "passive"))
      (node (ref "C22") (pin "1") (pinfunction "1_1") (pintype "passive"))
      (node (ref "D13") (pin "1") (pinfunction "K_1") (pintype "passive"))
      (node (ref "D31") (pin "2") (pinfunction "A_2") (pintype "passive"))
      (node (ref "MID_1") (pin "1") (pinfunction "1_1") (pintype "passive"))
      (node (ref "U5") (pin "31") (pinfunction "VEE2HS_31") (pintype "passive"))
      (node (ref "U5") (pin "32") (pinfunction "GND2HS_32") (pintype "passive"))
      (node (ref "U5") (pin "36") (pinfunction "VEE2HS_36") (pintype "passive"))
    )
    (net (code "7") (name "/D_L_2") (class "Default")
      (node (ref "C30") (pin "1") (pinfunction "1_1") (pintype "passive"))
      (node (ref "C32") (pin "1") (pinfunction "1_1") (pintype "passive"))
      (node (ref "D18") (pin "2") (pinfunction "A_2") (pintype "passive"))
      (node (ref "D20") (pin "1") (pinfunction "K_1") (pintype "passive"))
      (node (ref "MID_2") (pin "1") (pinfunction "1_1") (pintype "passive"))
      (node (ref "U3") (pin "31") (pinfunction "VEE2HS_31") (pintype "passive"))
      (node (ref "U3") (pin "32") (pinfunction "GND2HS_32") (pintype "passive"))
      (node (ref "U3") (pin "36") (pinfunction "VEE2HS_36") (pintype "passive"))
    )
    (net (code "8") (name "/D_SW") (class "Default")
      (node (ref "D3") (pin "1") (pinfunction "K_1") (pintype "passive"))
      (node (ref "D_SW") (pin "1") (pinfunction "1_1") (pintype "passive"))
    )
    (net (code "9") (name "/D_ZR") (class "Default")
      (node (ref "D10") (pin "1") (pinfunction "K_1") (pintype "passive"))
      (node (ref "D5") (pin "1") (pinfunction "K_1") (pintype "passive"))
      (node (ref "D_ZR") (pin "1") (pinfunction "1_1") (pintype "passive"))
    )
    (net (code "10") (name "/FLT") (class "Default")
      (node (ref "SIGNALS_CB") (pin "12") (pinfunction "12_12") (pintype "passive"))
    )
    (net (code "11") (name "/FLT_FD") (class "Default")
      (node (ref "U4") (pin "13") (pinfunction "~{FLT}_13") (pintype "output"))
    )
    (net (code "12") (name "/FLT_HS_1") (class "Default")
      (node (ref "U5") (pin "5") (pinfunction "~{FLTHS}_5") (pintype "output"))
    )
    (net (code "13") (name "/FLT_HS_2") (class "Default")
      (node (ref "U3") (pin "5") (pinfunction "~{FLTHS}_5") (pintype "output"))
    )
    (net (code "14") (name "/FLT_LS_1") (class "Default")
      (node (ref "U5") (pin "15") (pinfunction "~{FLTLS}_15") (pintype "output"))
    )
    (net (code "15") (name "/FLT_LS_2") (class "Default")
      (node (ref "U3") (pin "15") (pinfunction "~{FLTLS}_15") (pintype "output"))
    )
    (net (code "16") (name "/FLT_ZR1") (class "Default")
      (node (ref "U1") (pin "13") (pinfunction "~{FLT}_13") (pintype "output"))
    )
    (net (code "17") (name "/FLT_ZR2") (class "Default")
      (node (ref "U2") (pin "13") (pinfunction "~{FLT}_13") (pintype "output"))
    )
    (net (code "18") (name "/G_H_1") (class "Default")
      (node (ref "D30") (pin "2") (pinfunction "A_2") (pintype "passive"))
      (node (ref "G_H_1") (pin "1") (pinfunction "1_1") (pintype "passive"))
      (node (ref "R13") (pin "2") (pinfunction "2_2") (pintype "passive"))
      (node (ref "U5") (pin "35") (pinfunction "CLAMPHS_35") (pintype "output"))
    )
    (net (code "19") (name "/G_H_2") (class "Default")
      (node (ref "D17") (pin "2") (pinfunction "A_2") (pintype "passive"))
      (node (ref "G_H_2") (pin "1") (pinfunction "1_1") (pintype "passive"))
      (node (ref "R21") (pin "2") (pinfunction "2_2") (pintype "passive"))
      (node (ref "U3") (pin "35") (pinfunction "CLAMPHS_35") (pintype "output"))
    )
    (net (code "20") (name "/G_L_1") (class "Default")
      (node (ref "D35") (pin "2") (pinfunction "A_2") (pintype "passive"))
      (node (ref "G_L_1") (pin "1") (pinfunction "1_1") (pintype "passive"))
      (node (ref "R18") (pin "2") (pinfunction "2_2") (pintype "passive"))
      (node (ref "U5") (pin "25") (pinfunction "CLAMPLS_25") (pintype "output"))
    )
    (net (code "21") (name "/G_L_2") (class "Default")
      (node (ref "D21") (pin "2") (pinfunction "A_2") (pintype "passive"))
      (node (ref "G_L_2") (pin "1") (pinfunction "1_1") (pintype "passive"))
      (node (ref "R24") (pin "2") (pinfunction "2_2") (pintype "passive"))
      (node (ref "U3") (pin "25") (pinfunction "CLAMPLS_25") (pintype "output"))
    )
    (net (code "22") (name "/G_SB1") (class "Default")
      (node (ref "G_SB1") (pin "1") (pinfunction "1_1") (pintype "passive"))
      (node (ref "R2") (pin "2") (pinfunction "2_2") (pintype "passive"))
    )
    (net (code "23") (name "/G_SB2") (class "Default")
      (node (ref "G_SB2") (pin "1") (pinfunction "1_1") (pintype "passive"))
      (node (ref "R1") (pin "2") (pinfunction "2_2") (pintype "passive"))
    )
    (net (code "24") (name "/G_SW") (class "Default")
      (node (ref "D26") (pin "2") (pinfunction "A_2") (pintype "passive"))
      (node (ref "G_SW") (pin "1") (pinfunction "1_1") (pintype "passive"))
      (node (ref "R4") (pin "2") (pinfunction "2_2") (pintype "passive"))
      (node (ref "U4") (pin "7") (pinfunction "CLAMP_7") (pintype "output"))
    )
    (net (code "25") (name "/G_ZR1") (class "Default")
      (node (ref "D32") (pin "2") (pinfunction "A_2") (pintype "passive"))
      (node (ref "G_ZR1") (pin "1") (pinfunction "1_1") (pintype "passive"))
      (node (ref "R7") (pin "2") (pinfunction "2_2") (pintype "passive"))
      (node (ref "U1") (pin "7") (pinfunction "CLAMP_7") (pintype "output"))
    )
    (net (code "26") (name "/G_ZR2") (class "Default")
      (node (ref "D11") (pin "2") (pinfunction "A_2") (pintype "passive"))
      (node (ref "G_ZR2") (pin "1") (pinfunction "1_1") (pintype "passive"))
      (node (ref "R15") (pin "2") (pinfunction "2_2") (pintype "passive"))
      (node (ref "U2") (pin "7") (pinfunction "CLAMP_7") (pintype "output"))
    )
    (net (code "27") (name "/HS_1") (class "Default")
      (node (ref "R29") (pin "2") (pinfunction "2_2") (pintype "passive"))
      (node (ref "SIGNALS_CB") (pin "13") (pinfunction "13_13") (pintype "passive"))
      (node (ref "U5") (pin "2") (pinfunction "INHS+_2") (pintype "input"))
    )
    (net (code "28") (name "/HS_2") (class "Default")
      (node (ref "R26") (pin "2") (pinfunction "2_2") (pintype "passive"))
      (node (ref "SIGNALS_CB") (pin "10") (pinfunction "10_10") (pintype "passive"))
      (node (ref "U3") (pin "2") (pinfunction "INHS+_2") (pintype "input"))
    )
    (net (code "29") (name "/IN_FD") (class "Default")
      (node (ref "R28") (pin "2") (pinfunction "2_2") (pintype "passive"))
      (node (ref "SIGNALS_CB") (pin "8") (pinfunction "8_8") (pintype "passive"))
      (node (ref "U4") (pin "10") (pinfunction "IN+_10") (pintype "input"))
    )
    (net (code "30") (name "/IN_ZR1") (class "Default")
      (node (ref "R31") (pin "2") (pinfunction "2_2") (pintype "passive"))
      (node (ref "SIGNALS_CB") (pin "5") (pinfunction "5_5") (pintype "passive"))
      (node (ref "U1") (pin "10") (pinfunction "IN+_10") (pintype "input"))
    )
    (net (code "31") (name "/IN_ZR2") (class "Default")
      (node (ref "R30") (pin "2") (pinfunction "2_2") (pintype "passive"))
      (node (ref "SIGNALS_CB") (pin "6") (pinfunction "6_6") (pintype "passive"))
      (node (ref "U2") (pin "10") (pinfunction "IN+_10") (pintype "input"))
    )
    (net (code "32") (name "/LS_1") (class "Default")
      (node (ref "R33") (pin "2") (pinfunction "2_2") (pintype "passive"))
      (node (ref "SIGNALS_CB") (pin "14") (pinfunction "14_14") (pintype "passive"))
      (node (ref "U5") (pin "12") (pinfunction "INLS+_12") (pintype "input"))
    )
    (net (code "33") (name "/LS_2") (class "Default")
      (node (ref "R32") (pin "2") (pinfunction "2_2") (pintype "passive"))
      (node (ref "SIGNALS_CB") (pin "4") (pinfunction "4_4") (pintype "passive"))
      (node (ref "U3") (pin "12") (pinfunction "INLS+_12") (pintype "input"))
    )
    (net (code "34") (name "/RDY") (class "Default")
      (node (ref "SIGNALS_CB") (pin "11") (pinfunction "11_11") (pintype "passive"))
    )
    (net (code "35") (name "/RDY_FD") (class "Default")
      (node (ref "U4") (pin "12") (pinfunction "RDY_12") (pintype "output"))
    )
    (net (code "36") (name "/RDY_HS_1") (class "Default")
      (node (ref "U5") (pin "4") (pinfunction "RDYHS_4") (pintype "output"))
    )
    (net (code "37") (name "/RDY_HS_2") (class "Default")
      (node (ref "U3") (pin "4") (pinfunction "RDYHS_4") (pintype "output"))
    )
    (net (code "38") (name "/RDY_LS_1") (class "Default")
      (node (ref "U5") (pin "14") (pinfunction "RDYLS_14") (pintype "output"))
    )
    (net (code "39") (name "/RDY_LS_2") (class "Default")
      (node (ref "U3") (pin "14") (pinfunction "RDYLS_14") (pintype "output"))
    )
    (net (code "40") (name "/RDY_ZR1") (class "Default")
      (node (ref "U1") (pin "12") (pinfunction "RDY_12") (pintype "output"))
    )
    (net (code "41") (name "/RDY_ZR2") (class "Default")
      (node (ref "U2") (pin "12") (pinfunction "RDY_12") (pintype "output"))
    )
    (net (code "42") (name "/RST") (class "Default")
      (node (ref "R42") (pin "2") (pinfunction "2_2") (pintype "passive"))
      (node (ref "SIGNALS_CB") (pin "3") (pinfunction "3_3") (pintype "passive"))
      (node (ref "U1") (pin "14") (pinfunction "~{RST}_14") (pintype "input"))
      (node (ref "U2") (pin "14") (pinfunction "~{RST}_14") (pintype "input"))
      (node (ref "U3") (pin "16") (pinfunction "~{RSTLS}_16") (pintype "input"))
      (node (ref "U3") (pin "6") (pinfunction "~{RSTHS}_6") (pintype "input"))
      (node (ref "U4") (pin "14") (pinfunction "~{RST}_14") (pintype "input"))
      (node (ref "U5") (pin "16") (pinfunction "~{RSTLS}_16") (pintype "input"))
      (node (ref "U5") (pin "6") (pinfunction "~{RSTHS}_6") (pintype "input"))
    )
    (net (code "43") (name "/SB1") (class "Default")
      (node (ref "IC5") (pin "2") (pinfunction "HIN_2") (pintype "passive"))
      (node (ref "R34") (pin "2") (pinfunction "2_2") (pintype "passive"))
      (node (ref "SIGNALS_CB") (pin "7") (pinfunction "7_7") (pintype "passive"))
    )
    (net (code "44") (name "/SB2") (class "Default")
      (node (ref "IC4") (pin "2") (pinfunction "HIN_2") (pintype "passive"))
      (node (ref "R27") (pin "2") (pinfunction "2_2") (pintype "passive"))
      (node (ref "SIGNALS_CB") (pin "9") (pinfunction "9_9") (pintype "passive"))
    )
    (net (code "45") (name "/S_ZR1") (class "Default")
      (node (ref "C13") (pin "1") (pinfunction "1_1") (pintype "passive"))
      (node (ref "C15") (pin "1") (pinfunction "1_1") (pintype "passive"))
      (node (ref "D33") (pin "2") (pinfunction "A_2") (pintype "passive"))
      (node (ref "S_ZR1") (pin "1") (pinfunction "1_1") (pintype "passive"))
      (node (ref "U1") (pin "1") (pinfunction "VEE2_1") (pintype "passive"))
      (node (ref "U1") (pin "3") (pinfunction "GND2_3") (pintype "power_in"))
      (node (ref "U1") (pin "8") (pinfunction "VEE2_8") (pintype "passive"))
    )
    (net (code "46") (name "/S_ZR2") (class "Default")
      (node (ref "C17") (pin "1") (pinfunction "1_1") (pintype "passive"))
      (node (ref "C23") (pin "1") (pinfunction "1_1") (pintype "passive"))
      (node (ref "D12") (pin "2") (pinfunction "A_2") (pintype "passive"))
      (node (ref "S_ZR2") (pin "1") (pinfunction "1_1") (pintype "passive"))
      (node (ref "U2") (pin "1") (pinfunction "VEE2_1") (pintype "passive"))
      (node (ref "U2") (pin "3") (pinfunction "GND2_3") (pintype "power_in"))
      (node (ref "U2") (pin "8") (pinfunction "VEE2_8") (pintype "passive"))
    )
    (net (code "47") (name "/VGG_ZR1") (class "Default")
      (node (ref "C13") (pin "2") (pinfunction "2_2") (pintype "passive"))
      (node (ref "D28") (pin "1") (pinfunction "K_1") (pintype "passive"))
      (node (ref "R39") (pin "2") (pinfunction "2_2") (pintype "passive"))
      (node (ref "U1") (pin "5") (pinfunction "VCC2_5") (pintype "power_in"))
    )
    (net (code "48") (name "/VGG_ZR2") (class "Default")
      (node (ref "C17") (pin "2") (pinfunction "2_2") (pintype "passive"))
      (node (ref "D9") (pin "1") (pinfunction "K_1") (pintype "passive"))
      (node (ref "R40") (pin "2") (pinfunction "2_2") (pintype "passive"))
      (node (ref "U2") (pin "5") (pinfunction "VCC2_5") (pintype "power_in"))
    )
    (net (code "49") (name "DGND") (class "Default")
      (node (ref "C1") (pin "2") (pinfunction "2_2") (pintype "passive"))
      (node (ref "C11") (pin "2") (pinfunction "2_2") (pintype "passive"))
      (node (ref "C14") (pin "2") (pinfunction "2_2") (pintype "passive"))
      (node (ref "C2") (pin "2") (pinfunction "2_2") (pintype "passive"))
      (node (ref "C20") (pin "2") (pinfunction "2_2") (pintype "passive"))
      (node (ref "C21") (pin "2") (pinfunction "2_2") (pintype "passive"))
      (node (ref "C25") (pin "2") (pinfunction "2_2") (pintype "passive"))
      (node (ref "C31") (pin "2") (pinfunction "2_2") (pintype "passive"))
      (node (ref "C34") (pin "2") (pinfunction "2_2") (pintype "passive"))
      (node (ref "C9") (pin "2") (pinfunction "2_2") (pintype "passive"))
      (node (ref "D24") (pin "2") (pinfunction "A_2") (pintype "passive"))
      (node (ref "IC4") (pin "3") (pinfunction "LIN_3") (pintype "passive"))
      (node (ref "IC4") (pin "4") (pinfunction "COM_4") (pintype "passive"))
      (node (ref "IC5") (pin "3") (pinfunction "LIN_3") (pintype "passive"))
      (node (ref "IC5") (pin "4") (pinfunction "COM_4") (pintype "passive"))
      (node (ref "R26") (pin "1") (pinfunction "1_1") (pintype "passive"))
      (node (ref "R27") (pin "1") (pinfunction "1_1") (pintype "passive"))
      (node (ref "R28") (pin "1") (pinfunction "1_1") (pintype "passive"))
      (node (ref "R29") (pin "1") (pinfunction "1_1") (pintype "passive"))
      (node (ref "R30") (pin "1") (pinfunction "1_1") (pintype "passive"))
      (node (ref "R31") (pin "1") (pinfunction "1_1") (pintype "passive"))
      (node (ref "R32") (pin "1") (pinfunction "1_1") (pintype "passive"))
      (node (ref "R33") (pin "1") (pinfunction "1_1") (pintype "passive"))
      (node (ref "R34") (pin "1") (pinfunction "1_1") (pintype "passive"))
      (node (ref "R42") (pin "1") (pinfunction "1_1") (pintype "passive"))
      (node (ref "SIGNALS_CB") (pin "1") (pinfunction "1_1") (pintype "passive"))
      (node (ref "SIGNALS_CB") (pin "15") (pinfunction "15_15") (pintype "passive"))
      (node (ref "U1") (pin "11") (pinfunction "IN-_11") (pintype "input"))
      (node (ref "U1") (pin "16") (pinfunction "GND1_16") (pintype "power_in"))
      (node (ref "U1") (pin "9") (pinfunction "GND1_9") (pintype "power_in"))
      (node (ref "U2") (pin "11") (pinfunction "IN-_11") (pintype "input"))
      (node (ref "U2") (pin "16") (pinfunction "GND1_16") (pintype "power_in"))
      (node (ref "U2") (pin "9") (pinfunction "GND1_9") (pintype "power_in"))
      (node (ref "U3") (pin "1") (pinfunction "GND1_1") (pintype "passive"))
      (node (ref "U3") (pin "11") (pinfunction "GND1_11") (pintype "passive"))
      (node (ref "U3") (pin "13") (pinfunction "INLS-_13") (pintype "input"))
      (node (ref "U3") (pin "18") (pinfunction "GND1_18") (pintype "passive"))
      (node (ref "U3") (pin "3") (pinfunction "INHS-_3") (pintype "input"))
      (node (ref "U3") (pin "8") (pinfunction "GND1_8") (pintype "passive"))
      (node (ref "U4") (pin "11") (pinfunction "IN-_11") (pintype "input"))
      (node (ref "U4") (pin "16") (pinfunction "GND1_16") (pintype "power_in"))
      (node (ref "U4") (pin "9") (pinfunction "GND1_9") (pintype "power_in"))
      (node (ref "U5") (pin "1") (pinfunction "GND1_1") (pintype "passive"))
      (node (ref "U5") (pin "11") (pinfunction "GND1_11") (pintype "passive"))
      (node (ref "U5") (pin "13") (pinfunction "INLS-_13") (pintype "input"))
      (node (ref "U5") (pin "18") (pinfunction "GND1_18") (pintype "passive"))
      (node (ref "U5") (pin "3") (pinfunction "INHS-_3") (pintype "input"))
      (node (ref "U5") (pin "8") (pinfunction "GND1_8") (pintype "passive"))
    )
    (net (code "50") (name "EARTH") (class "Default")
      (node (ref "J1") (pin "1") (pinfunction "1_1") (pintype "passive"))
      (node (ref "J1") (pin "2") (pinfunction "2_2") (pintype "passive"))
      (node (ref "SIGNALS_CB") (pin "MH1") (pinfunction "MH1_MH1") (pintype "passive"))
      (node (ref "SIGNALS_CB") (pin "MH2") (pinfunction "MH2_MH2") (pintype "passive"))
    )
    (net (code "51") (name "GND_ISO2") (class "Default")
      (node (ref "C10") (pin "1") (pinfunction "1_1") (pintype "passive"))
      (node (ref "C3") (pin "1") (pinfunction "1_1") (pintype "passive"))
      (node (ref "D25") (pin "2") (pinfunction "A_2") (pintype "passive"))
      (node (ref "S_SW") (pin "1") (pinfunction "1_1") (pintype "passive"))
      (node (ref "U4") (pin "1") (pinfunction "VEE2_1") (pintype "passive"))
      (node (ref "U4") (pin "3") (pinfunction "GND2_3") (pintype "power_in"))
      (node (ref "U4") (pin "8") (pinfunction "VEE2_8") (pintype "passive"))
    )
    (net (code "52") (name "GND_ISO3") (class "Default")
      (node (ref "C12") (pin "1") (pinfunction "1_1") (pintype "passive"))
      (node (ref "C16") (pin "1") (pinfunction "1_1") (pintype "passive"))
      (node (ref "C18") (pin "1") (pinfunction "1_1") (pintype "passive"))
      (node (ref "C24") (pin "1") (pinfunction "1_1") (pintype "passive"))
      (node (ref "C26") (pin "1") (pinfunction "1_1") (pintype "passive"))
      (node (ref "C27") (pin "1") (pinfunction "1_1") (pintype "passive"))
      (node (ref "C28") (pin "1") (pinfunction "1_1") (pintype "passive"))
      (node (ref "C29") (pin "1") (pinfunction "1_1") (pintype "passive"))
      (node (ref "C33") (pin "1") (pinfunction "1_1") (pintype "passive"))
      (node (ref "C35") (pin "1") (pinfunction "1_1") (pintype "passive"))
      (node (ref "D22") (pin "2") (pinfunction "A_2") (pintype "passive"))
      (node (ref "D37") (pin "2") (pinfunction "A_2") (pintype "passive"))
      (node (ref "S_L_1") (pin "1") (pinfunction "1_1") (pintype "passive"))
      (node (ref "S_L_2") (pin "1") (pinfunction "1_1") (pintype "passive"))
      (node (ref "U3") (pin "19") (pinfunction "VEE2LS_19") (pintype "passive"))
      (node (ref "U3") (pin "21") (pinfunction "GND2LS_21") (pintype "passive"))
      (node (ref "U3") (pin "24") (pinfunction "VEE2LS_24") (pintype "passive"))
      (node (ref "U5") (pin "19") (pinfunction "VEE2LS_19") (pintype "passive"))
      (node (ref "U5") (pin "21") (pinfunction "GND2LS_21") (pintype "passive"))
      (node (ref "U5") (pin "24") (pinfunction "VEE2LS_24") (pintype "passive"))
    )
    (net (code "53") (name "Net-(D1-K)") (class "Default")
      (node (ref "D1") (pin "1") (pinfunction "K_1") (pintype "passive"))
      (node (ref "R35") (pin "1") (pinfunction "1_1") (pintype "passive"))
    )
    (net (code "54") (name "Net-(D2-K)") (class "Default")
      (node (ref "D2") (pin "1") (pinfunction "K_1") (pintype "passive"))
      (node (ref "R36") (pin "1") (pinfunction "1_1") (pintype "passive"))
    )
    (net (code "55") (name "Net-(D3-A)") (class "Default")
      (node (ref "D3") (pin "2") (pinfunction "A_2") (pintype "passive"))
      (node (ref "R3") (pin "2") (pinfunction "2_2") (pintype "passive"))
    )
    (net (code "56") (name "Net-(D4-K)") (class "Default")
      (node (ref "D4") (pin "1") (pinfunction "K_1") (pintype "passive"))
      (node (ref "R39") (pin "1") (pinfunction "1_1") (pintype "passive"))
    )
    (net (code "57") (name "Net-(D5-A)") (class "Default")
      (node (ref "D5") (pin "2") (pinfunction "A_2") (pintype "passive"))
      (node (ref "R6") (pin "2") (pinfunction "2_2") (pintype "passive"))
    )
    (net (code "58") (name "Net-(D6-K)") (class "Default")
      (node (ref "D6") (pin "1") (pinfunction "K_1") (pintype "passive"))
      (node (ref "R40") (pin "1") (pinfunction "1_1") (pintype "passive"))
    )
    (net (code "59") (name "Net-(D7-K)") (class "Default")
      (node (ref "D7") (pin "1") (pinfunction "K_1") (pintype "passive"))
      (node (ref "R38") (pin "1") (pinfunction "1_1") (pintype "passive"))
    )
    (net (code "60") (name "Net-(D8-A)") (class "Default")
      (node (ref "D8") (pin "2") (pinfunction "A_2") (pintype "passive"))
      (node (ref "R11") (pin "2") (pinfunction "2_2") (pintype "passive"))
    )
    (net (code "61") (name "Net-(D10-A)") (class "Default")
      (node (ref "D10") (pin "2") (pinfunction "A_2") (pintype "passive"))
      (node (ref "R12") (pin "2") (pinfunction "2_2") (pintype "passive"))
    )
    (net (code "62") (name "Net-(D11-K)") (class "Default")
      (node (ref "D11") (pin "1") (pinfunction "K_1") (pintype "passive"))
      (node (ref "R16") (pin "2") (pinfunction "2_2") (pintype "passive"))
    )
    (net (code "63") (name "Net-(D12-K)") (class "Default")
      (node (ref "C23") (pin "2") (pinfunction "2_2") (pintype "passive"))
      (node (ref "D12") (pin "1") (pinfunction "K_1") (pintype "passive"))
      (node (ref "D9") (pin "2") (pinfunction "A_2") (pintype "passive"))
      (node (ref "R12") (pin "1") (pinfunction "1_1") (pintype "passive"))
      (node (ref "U2") (pin "2") (pinfunction "DESAT_2") (pintype "input"))
    )
    (net (code "64") (name "Net-(D13-A)") (class "Default")
      (node (ref "D13") (pin "2") (pinfunction "A_2") (pintype "passive"))
      (node (ref "R17") (pin "2") (pinfunction "2_2") (pintype "passive"))
    )
    (net (code "65") (name "Net-(D14-K)") (class "Default")
      (node (ref "D14") (pin "1") (pinfunction "K_1") (pintype "passive"))
      (node (ref "R37") (pin "1") (pinfunction "1_1") (pintype "passive"))
    )
    (net (code "66") (name "Net-(D15-A)") (class "Default")
      (node (ref "D15") (pin "2") (pinfunction "A_2") (pintype "passive"))
      (node (ref "R20") (pin "2") (pinfunction "2_2") (pintype "passive"))
    )
    (net (code "67") (name "Net-(D16-A)") (class "Default")
      (node (ref "C32") (pin "2") (pinfunction "2_2") (pintype "passive"))
      (node (ref "D16") (pin "2") (pinfunction "A_2") (pintype "passive"))
      (node (ref "D18") (pin "1") (pinfunction "K_1") (pintype "passive"))
      (node (ref "R20") (pin "1") (pinfunction "1_1") (pintype "passive"))
      (node (ref "U3") (pin "30") (pinfunction "DESATHS_30") (pintype "input"))
    )
    (net (code "68") (name "Net-(D16-K)") (class "Default")
      (node (ref "C30") (pin "2") (pinfunction "2_2") (pintype "passive"))
      (node (ref "D16") (pin "1") (pinfunction "K_1") (pintype "passive"))
      (node (ref "R37") (pin "2") (pinfunction "2_2") (pintype "passive"))
      (node (ref "U3") (pin "33") (pinfunction "VCC2HS_33") (pintype "passive"))
    )
    (net (code "69") (name "Net-(D17-K)") (class "Default")
      (node (ref "D17") (pin "1") (pinfunction "K_1") (pintype "passive"))
      (node (ref "R22") (pin "2") (pinfunction "2_2") (pintype "passive"))
    )
    (net (code "70") (name "Net-(D19-A)") (class "Default")
      (node (ref "C35") (pin "2") (pinfunction "2_2") (pintype "passive"))
      (node (ref "D19") (pin "2") (pinfunction "A_2") (pintype "passive"))
      (node (ref "D22") (pin "1") (pinfunction "K_1") (pintype "passive"))
      (node (ref "R23") (pin "1") (pinfunction "1_1") (pintype "passive"))
      (node (ref "U3") (pin "20") (pinfunction "DESATLS_20") (pintype "input"))
    )
    (net (code "71") (name "Net-(D20-A)") (class "Default")
      (node (ref "D20") (pin "2") (pinfunction "A_2") (pintype "passive"))
      (node (ref "R23") (pin "2") (pinfunction "2_2") (pintype "passive"))
    )
    (net (code "72") (name "Net-(D21-K)") (class "Default")
      (node (ref "D21") (pin "1") (pinfunction "K_1") (pintype "passive"))
      (node (ref "R25") (pin "2") (pinfunction "2_2") (pintype "passive"))
    )
    (net (code "73") (name "Net-(D23-A)") (class "Default")
      (node (ref "C10") (pin "2") (pinfunction "2_2") (pintype "passive"))
      (node (ref "D23") (pin "2") (pinfunction "A_2") (pintype "passive"))
      (node (ref "D25") (pin "1") (pinfunction "K_1") (pintype "passive"))
      (node (ref "R3") (pin "1") (pinfunction "1_1") (pintype "passive"))
      (node (ref "U4") (pin "2") (pinfunction "DESAT_2") (pintype "input"))
    )
    (net (code "74") (name "Net-(D26-K)") (class "Default")
      (node (ref "D26") (pin "1") (pinfunction "K_1") (pintype "passive"))
      (node (ref "R5") (pin "2") (pinfunction "2_2") (pintype "passive"))
    )
    (net (code "75") (name "Net-(D28-A)") (class "Default")
      (node (ref "C15") (pin "2") (pinfunction "2_2") (pintype "passive"))
      (node (ref "D28") (pin "2") (pinfunction "A_2") (pintype "passive"))
      (node (ref "D33") (pin "1") (pinfunction "K_1") (pintype "passive"))
      (node (ref "R6") (pin "1") (pinfunction "1_1") (pintype "passive"))
      (node (ref "U1") (pin "2") (pinfunction "DESAT_2") (pintype "input"))
    )
    (net (code "76") (name "Net-(D29-A)") (class "Default")
      (node (ref "C22") (pin "2") (pinfunction "2_2") (pintype "passive"))
      (node (ref "D29") (pin "2") (pinfunction "A_2") (pintype "passive"))
      (node (ref "D31") (pin "1") (pinfunction "K_1") (pintype "passive"))
      (node (ref "R11") (pin "1") (pinfunction "1_1") (pintype "passive"))
      (node (ref "U5") (pin "30") (pinfunction "DESATHS_30") (pintype "input"))
    )
    (net (code "77") (name "Net-(D29-K)") (class "Default")
      (node (ref "C19") (pin "2") (pinfunction "2_2") (pintype "passive"))
      (node (ref "D29") (pin "1") (pinfunction "K_1") (pintype "passive"))
      (node (ref "R38") (pin "2") (pinfunction "2_2") (pintype "passive"))
      (node (ref "U5") (pin "33") (pinfunction "VCC2HS_33") (pintype "passive"))
    )
    (net (code "78") (name "Net-(D30-K)") (class "Default")
      (node (ref "D30") (pin "1") (pinfunction "K_1") (pintype "passive"))
      (node (ref "R14") (pin "2") (pinfunction "2_2") (pintype "passive"))
    )
    (net (code "79") (name "Net-(D32-K)") (class "Default")
      (node (ref "D32") (pin "1") (pinfunction "K_1") (pintype "passive"))
      (node (ref "R10") (pin "2") (pinfunction "2_2") (pintype "passive"))
    )
    (net (code "80") (name "Net-(D34-A)") (class "Default")
      (node (ref "C26") (pin "2") (pinfunction "2_2") (pintype "passive"))
      (node (ref "D34") (pin "2") (pinfunction "A_2") (pintype "passive"))
      (node (ref "D37") (pin "1") (pinfunction "K_1") (pintype "passive"))
      (node (ref "R17") (pin "1") (pinfunction "1_1") (pintype "passive"))
      (node (ref "U5") (pin "20") (pinfunction "DESATLS_20") (pintype "input"))
    )
    (net (code "81") (name "Net-(D35-K)") (class "Default")
      (node (ref "D35") (pin "1") (pinfunction "K_1") (pintype "passive"))
      (node (ref "R19") (pin "2") (pinfunction "2_2") (pintype "passive"))
    )
    (net (code "82") (name "Net-(IC4-HO)") (class "Default")
      (node (ref "IC4") (pin "7") (pinfunction "HO_7") (pintype "passive"))
      (node (ref "R1") (pin "1") (pinfunction "1_1") (pintype "passive"))
    )
    (net (code "83") (name "Net-(IC4-VB)") (class "Default")
      (node (ref "C4") (pin "2") (pinfunction "2_2") (pintype "passive"))
      (node (ref "IC4") (pin "8") (pinfunction "VB_8") (pintype "passive"))
      (node (ref "R35") (pin "2") (pinfunction "2_2") (pintype "passive"))
    )
    (net (code "84") (name "Net-(IC5-HO)") (class "Default")
      (node (ref "IC5") (pin "7") (pinfunction "HO_7") (pintype "passive"))
      (node (ref "R2") (pin "1") (pinfunction "1_1") (pintype "passive"))
    )
    (net (code "85") (name "Net-(IC5-VB)") (class "Default")
      (node (ref "C5") (pin "2") (pinfunction "2_2") (pintype "passive"))
      (node (ref "IC5") (pin "8") (pinfunction "VB_8") (pintype "passive"))
      (node (ref "R36") (pin "2") (pinfunction "2_2") (pintype "passive"))
    )
    (net (code "86") (name "Net-(U1-OUT)") (class "Default")
      (node (ref "R10") (pin "1") (pinfunction "1_1") (pintype "passive"))
      (node (ref "R7") (pin "1") (pinfunction "1_1") (pintype "passive"))
      (node (ref "U1") (pin "6") (pinfunction "OUT_6") (pintype "output"))
    )
    (net (code "87") (name "Net-(U2-OUT)") (class "Default")
      (node (ref "R15") (pin "1") (pinfunction "1_1") (pintype "passive"))
      (node (ref "R16") (pin "1") (pinfunction "1_1") (pintype "passive"))
      (node (ref "U2") (pin "6") (pinfunction "OUT_6") (pintype "output"))
    )
    (net (code "88") (name "Net-(U3-OUTHS)") (class "Default")
      (node (ref "R21") (pin "1") (pinfunction "1_1") (pintype "passive"))
      (node (ref "R22") (pin "1") (pinfunction "1_1") (pintype "passive"))
      (node (ref "U3") (pin "34") (pinfunction "OUTHS_34") (pintype "output"))
    )
    (net (code "89") (name "Net-(U3-OUTLS)") (class "Default")
      (node (ref "R24") (pin "1") (pinfunction "1_1") (pintype "passive"))
      (node (ref "R25") (pin "1") (pinfunction "1_1") (pintype "passive"))
      (node (ref "U3") (pin "23") (pinfunction "OUTLS_23") (pintype "output"))
    )
    (net (code "90") (name "Net-(U4-OUT)") (class "Default")
      (node (ref "R4") (pin "1") (pinfunction "1_1") (pintype "passive"))
      (node (ref "R5") (pin "1") (pinfunction "1_1") (pintype "passive"))
      (node (ref "U4") (pin "6") (pinfunction "OUT_6") (pintype "output"))
    )
    (net (code "91") (name "Net-(U5-OUTHS)") (class "Default")
      (node (ref "R13") (pin "1") (pinfunction "1_1") (pintype "passive"))
      (node (ref "R14") (pin "1") (pinfunction "1_1") (pintype "passive"))
      (node (ref "U5") (pin "34") (pinfunction "OUTHS_34") (pintype "output"))
    )
    (net (code "92") (name "Net-(U5-OUTLS)") (class "Default")
      (node (ref "R18") (pin "1") (pinfunction "1_1") (pintype "passive"))
      (node (ref "R19") (pin "1") (pinfunction "1_1") (pintype "passive"))
      (node (ref "U5") (pin "23") (pinfunction "OUTLS_23") (pintype "output"))
    )
    (net (code "93") (name "unconnected-(FID1-Pad1)") (class "Default")
      (node (ref "FID1") (pin "1") (pinfunction "1_1") (pintype "power_in+no_connect"))
    )
    (net (code "94") (name "unconnected-(FID2-Pad1)") (class "Default")
      (node (ref "FID2") (pin "1") (pinfunction "1_1") (pintype "power_in+no_connect"))
    )
    (net (code "95") (name "unconnected-(IC4-LO-Pad5)") (class "Default")
      (node (ref "IC4") (pin "5") (pinfunction "LO_5") (pintype "passive+no_connect"))
    )
    (net (code "96") (name "unconnected-(IC5-LO-Pad5)") (class "Default")
      (node (ref "IC5") (pin "5") (pinfunction "LO_5") (pintype "passive+no_connect"))
    )
    (net (code "97") (name "unconnected-(U1-NC-Pad4)") (class "Default")
      (node (ref "U1") (pin "4") (pinfunction "NC_4") (pintype "passive+no_connect"))
    )
    (net (code "98") (name "unconnected-(U2-NC-Pad4)") (class "Default")
      (node (ref "U2") (pin "4") (pinfunction "NC_4") (pintype "passive+no_connect"))
    )
    (net (code "99") (name "unconnected-(U3-NC-Pad9)") (class "Default")
      (node (ref "U3") (pin "9") (pinfunction "NC_9") (pintype "passive"))
    )
    (net (code "100") (name "unconnected-(U3-NC-Pad10)") (class "Default")
      (node (ref "U3") (pin "10") (pinfunction "NC_10") (pintype "passive"))
    )
    (net (code "101") (name "unconnected-(U4-NC-Pad4)") (class "Default")
      (node (ref "U4") (pin "4") (pinfunction "NC_4") (pintype "passive+no_connect"))
    )
    (net (code "102") (name "unconnected-(U5-NC-Pad9)") (class "Default")
      (node (ref "U5") (pin "9") (pinfunction "NC_9") (pintype "passive"))
    )
    (net (code "103") (name "unconnected-(U5-NC-Pad10)") (class "Default")
      (node (ref "U5") (pin "10") (pinfunction "NC_10") (pintype "passive"))
    )
  )
)
